# cpu.net
KiCad netlist of a schematic drawn in Altium Designer
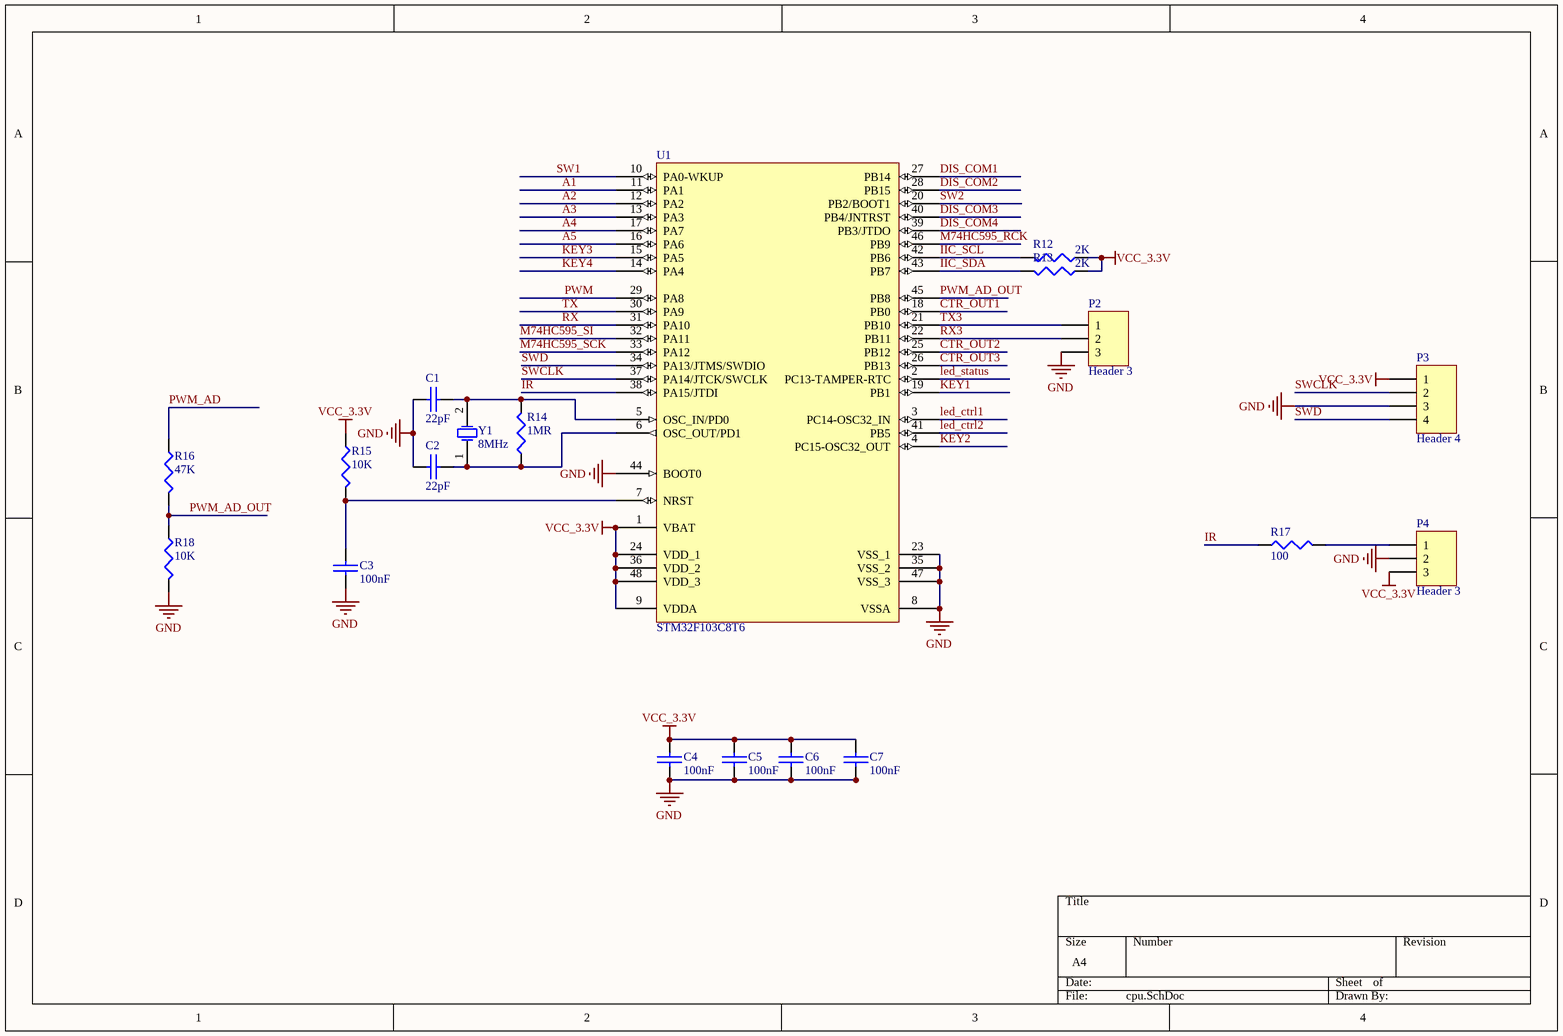
[diagram p0: cpu.SchDoc]

(export (version "E")
  (design (tool "Eeschema 10.0.6"))
  (components
    (comp (ref "C1")
      (value "22pF")
      (footprint "0805c")
      (description "Capacitor")
      (libsource (lib "SM") (part "CAP"))
    )
    (comp (ref "C2")
      (value "22pF")
      (footprint "0805c")
      (description "Capacitor")
      (libsource (lib "SM") (part "CAP"))
    )
    (comp (ref "C3")
      (value "100nF")
      (footprint "0805c")
      (description "Capacitor")
      (libsource (lib "SM") (part "CAP"))
    )
    (comp (ref "C4")
      (value "100nF")
      (footprint "0805c")
      (description "Capacitor")
      (libsource (lib "SM") (part "CAP"))
    )
    (comp (ref "C5")
      (value "100nF")
      (footprint "0805c")
      (description "Capacitor")
      (libsource (lib "SM") (part "CAP"))
    )
    (comp (ref "C6")
      (value "100nF")
      (footprint "0805c")
      (description "Capacitor")
      (libsource (lib "SM") (part "CAP"))
    )
    (comp (ref "C7")
      (value "100nF")
      (footprint "0805c")
      (description "Capacitor")
      (libsource (lib "SM") (part "CAP"))
    )
    (comp (ref "P2")
      (value "Header 3")
      (footprint "HDR1X3")
      (description "Header, 3-Pin")
      (fields (field (name "PUBLISHER") "Altium Limited"))
      (libsource (lib "Miscellaneous Connectors") (part "Header 3"))
    )
    (comp (ref "P3")
      (value "Header 4")
      (footprint "HDR1X4")
      (description "Header, 4-Pin")
      (fields (field (name "PUBLISHER") "Altium Limited"))
      (libsource (lib "Miscellaneous Connectors") (part "Header 4"))
    )
    (comp (ref "P4")
      (value "Header 3")
      (footprint "HDR1X3")
      (description "Header, 3-Pin")
      (fields (field (name "PUBLISHER") "Altium Limited"))
      (libsource (lib "Miscellaneous Connectors") (part "Header 3"))
    )
    (comp (ref "R12")
      (value "2K")
      (footprint "0805R")
      (description "Resistor")
      (fields (field (name "PUBLISHER") "Altium Limited"))
      (libsource (lib "SM") (part "Res3"))
    )
    (comp (ref "R13")
      (value "2K")
      (footprint "0805R")
      (description "Resistor")
      (fields (field (name "PUBLISHER") "Altium Limited"))
      (libsource (lib "SM") (part "Res3"))
    )
    (comp (ref "R14")
      (value "1MR")
      (footprint "0805R")
      (description "Resistor")
      (fields (field (name "PUBLISHER") "Altium Limited"))
      (libsource (lib "SM") (part "Res3"))
    )
    (comp (ref "R15")
      (value "10K")
      (footprint "0805R")
      (description "Resistor")
      (fields (field (name "PUBLISHER") "Altium Limited"))
      (libsource (lib "SM") (part "Res3"))
    )
    (comp (ref "R16")
      (value "47K")
      (footprint "0805R")
      (description "Resistor")
      (fields (field (name "PUBLISHER") "Altium Limited"))
      (libsource (lib "SM") (part "Res3"))
    )
    (comp (ref "R17")
      (value "100")
      (footprint "0805R")
      (description "Resistor")
      (fields (field (name "PUBLISHER") "Altium Limited"))
      (libsource (lib "SM") (part "Res3"))
    )
    (comp (ref "R18")
      (value "10K")
      (footprint "0805R")
      (description "Resistor")
      (fields (field (name "PUBLISHER") "Altium Limited"))
      (libsource (lib "SM") (part "Res3"))
    )
    (comp (ref "U1")
      (value "STM32F103C8T6")
      (footprint "TQFP-48")
      (description "STM32 ARM-based 32-bit MCU with 64 Kbytes Flash, 48-pin LQFP, Industrial Temperature")
      (fields (field (name "PUBLISHER") "Altium Limited"))
      (libsource (lib "ST Microcontroller 32-Bit STM32") (part "STM32F103C8T6"))
    )
    (comp (ref "Y1")
      (value "8MHz")
      (footprint "SMT5032")
      (description "Crystal Oscillator")
      (fields (field (name "PUBLISHER") "Altium Limited"))
      (libsource (lib "Miscellaneous Devices") (part "XTAL"))
    )
  )
  (nets
    (net (code "1") (name "/A1") (class "Default")
      (node (ref "U1") (pin "11") (pinfunction "PA1_11") (pintype "bidirectional"))
    )
    (net (code "2") (name "/A2") (class "Default")
      (node (ref "U1") (pin "12") (pinfunction "PA2_12") (pintype "bidirectional"))
    )
    (net (code "3") (name "/A3") (class "Default")
      (node (ref "U1") (pin "13") (pinfunction "PA3_13") (pintype "bidirectional"))
    )
    (net (code "4") (name "/A4") (class "Default")
      (node (ref "U1") (pin "17") (pinfunction "PA7_17") (pintype "bidirectional"))
    )
    (net (code "5") (name "/A5") (class "Default")
      (node (ref "U1") (pin "16") (pinfunction "PA6_16") (pintype "bidirectional"))
    )
    (net (code "6") (name "/CTR_OUT1") (class "Default")
      (node (ref "U1") (pin "18") (pinfunction "PB0_18") (pintype "bidirectional"))
    )
    (net (code "7") (name "/CTR_OUT2") (class "Default")
      (node (ref "U1") (pin "25") (pinfunction "PB12_25") (pintype "bidirectional"))
    )
    (net (code "8") (name "/CTR_OUT3") (class "Default")
      (node (ref "U1") (pin "26") (pinfunction "PB13_26") (pintype "bidirectional"))
    )
    (net (code "9") (name "/DIS_COM1") (class "Default")
      (node (ref "U1") (pin "27") (pinfunction "PB14_27") (pintype "bidirectional"))
    )
    (net (code "10") (name "/DIS_COM2") (class "Default")
      (node (ref "U1") (pin "28") (pinfunction "PB15_28") (pintype "bidirectional"))
    )
    (net (code "11") (name "/DIS_COM3") (class "Default")
      (node (ref "U1") (pin "40") (pinfunction "PB4/JNTRST_40") (pintype "bidirectional"))
    )
    (net (code "12") (name "/DIS_COM4") (class "Default")
      (node (ref "U1") (pin "39") (pinfunction "PB3/JTDO_39") (pintype "bidirectional"))
    )
    (net (code "13") (name "/IIC_SCL") (class "Default")
      (node (ref "R12") (pin "2") (pinfunction "2_2") (pintype "passive"))
      (node (ref "U1") (pin "42") (pinfunction "PB6_42") (pintype "bidirectional"))
    )
    (net (code "14") (name "/IIC_SDA") (class "Default")
      (node (ref "R13") (pin "2") (pinfunction "2_2") (pintype "passive"))
      (node (ref "U1") (pin "43") (pinfunction "PB7_43") (pintype "bidirectional"))
    )
    (net (code "15") (name "/IR") (class "Default")
      (node (ref "R17") (pin "1") (pinfunction "1_1") (pintype "passive"))
      (node (ref "U1") (pin "38") (pinfunction "PA15/JTDI_38") (pintype "bidirectional"))
    )
    (net (code "16") (name "/KEY1") (class "Default")
      (node (ref "U1") (pin "19") (pinfunction "PB1_19") (pintype "bidirectional"))
    )
    (net (code "17") (name "/KEY2") (class "Default")
      (node (ref "U1") (pin "4") (pinfunction "PC15-OSC32_OUT_4") (pintype "bidirectional"))
    )
    (net (code "18") (name "/KEY3") (class "Default")
      (node (ref "U1") (pin "15") (pinfunction "PA5_15") (pintype "bidirectional"))
    )
    (net (code "19") (name "/KEY4") (class "Default")
      (node (ref "U1") (pin "14") (pinfunction "PA4_14") (pintype "bidirectional"))
    )
    (net (code "20") (name "/M74HC595_RCK") (class "Default")
      (node (ref "U1") (pin "46") (pinfunction "PB9_46") (pintype "bidirectional"))
    )
    (net (code "21") (name "/M74HC595_SCK") (class "Default")
      (node (ref "U1") (pin "33") (pinfunction "PA12_33") (pintype "bidirectional"))
    )
    (net (code "22") (name "/M74HC595_SI") (class "Default")
      (node (ref "U1") (pin "32") (pinfunction "PA11_32") (pintype "bidirectional"))
    )
    (net (code "23") (name "/PWM") (class "Default")
      (node (ref "U1") (pin "29") (pinfunction "PA8_29") (pintype "bidirectional"))
    )
    (net (code "24") (name "/PWM_AD") (class "Default")
      (node (ref "R16") (pin "1") (pinfunction "1_1") (pintype "passive"))
    )
    (net (code "25") (name "/PWM_AD_OUT") (class "Default")
      (node (ref "R16") (pin "2") (pinfunction "2_2") (pintype "passive"))
      (node (ref "R18") (pin "1") (pinfunction "1_1") (pintype "passive"))
      (node (ref "U1") (pin "45") (pinfunction "PB8_45") (pintype "bidirectional"))
    )
    (net (code "26") (name "/RX") (class "Default")
      (node (ref "U1") (pin "31") (pinfunction "PA10_31") (pintype "bidirectional"))
    )
    (net (code "27") (name "/RX3") (class "Default")
      (node (ref "P2") (pin "2") (pinfunction "2_2") (pintype "passive"))
      (node (ref "U1") (pin "22") (pinfunction "PB11_22") (pintype "bidirectional"))
    )
    (net (code "28") (name "/SW1") (class "Default")
      (node (ref "U1") (pin "10") (pinfunction "PA0-WKUP_10") (pintype "bidirectional"))
    )
    (net (code "29") (name "/SW2") (class "Default")
      (node (ref "U1") (pin "20") (pinfunction "PB2/BOOT1_20") (pintype "bidirectional"))
    )
    (net (code "30") (name "/SWCLK") (class "Default")
      (node (ref "P3") (pin "2") (pinfunction "2_2") (pintype "passive"))
      (node (ref "U1") (pin "37") (pinfunction "PA14/JTCK/SWCLK_37") (pintype "bidirectional"))
    )
    (net (code "31") (name "/SWD") (class "Default")
      (node (ref "P3") (pin "4") (pinfunction "4_4") (pintype "passive"))
      (node (ref "U1") (pin "34") (pinfunction "PA13/JTMS/SWDIO_34") (pintype "bidirectional"))
    )
    (net (code "32") (name "/TX") (class "Default")
      (node (ref "U1") (pin "30") (pinfunction "PA9_30") (pintype "bidirectional"))
    )
    (net (code "33") (name "/TX3") (class "Default")
      (node (ref "P2") (pin "1") (pinfunction "1_1") (pintype "passive"))
      (node (ref "U1") (pin "21") (pinfunction "PB10_21") (pintype "bidirectional"))
    )
    (net (code "34") (name "/led_ctrl1") (class "Default")
      (node (ref "U1") (pin "3") (pinfunction "PC14-OSC32_IN_3") (pintype "bidirectional"))
    )
    (net (code "35") (name "/led_ctrl2") (class "Default")
      (node (ref "U1") (pin "41") (pinfunction "PB5_41") (pintype "bidirectional"))
    )
    (net (code "36") (name "/led_status") (class "Default")
      (node (ref "U1") (pin "2") (pinfunction "PC13-TAMPER-RTC_2") (pintype "bidirectional"))
    )
    (net (code "37") (name "GND") (class "Default")
      (node (ref "C1") (pin "1") (pinfunction "1_1") (pintype "passive"))
      (node (ref "C2") (pin "1") (pinfunction "1_1") (pintype "passive"))
      (node (ref "C3") (pin "1") (pinfunction "1_1") (pintype "passive"))
      (node (ref "C4") (pin "1") (pinfunction "1_1") (pintype "passive"))
      (node (ref "C5") (pin "1") (pinfunction "1_1") (pintype "passive"))
      (node (ref "C6") (pin "1") (pinfunction "1_1") (pintype "passive"))
      (node (ref "C7") (pin "1") (pinfunction "1_1") (pintype "passive"))
      (node (ref "P2") (pin "3") (pinfunction "3_3") (pintype "passive"))
      (node (ref "P3") (pin "3") (pinfunction "3_3") (pintype "passive"))
      (node (ref "P4") (pin "2") (pinfunction "2_2") (pintype "passive"))
      (node (ref "R18") (pin "2") (pinfunction "2_2") (pintype "passive"))
      (node (ref "U1") (pin "23") (pinfunction "VSS_1_23") (pintype "power_in"))
      (node (ref "U1") (pin "35") (pinfunction "VSS_2_35") (pintype "power_in"))
      (node (ref "U1") (pin "44") (pinfunction "BOOT0_44") (pintype "input"))
      (node (ref "U1") (pin "47") (pinfunction "VSS_3_47") (pintype "power_in"))
      (node (ref "U1") (pin "8") (pinfunction "VSSA_8") (pintype "power_in"))
    )
    (net (code "38") (name "Net-(P4-Pad1)") (class "Default")
      (node (ref "P4") (pin "1") (pinfunction "1_1") (pintype "passive"))
      (node (ref "R17") (pin "2") (pinfunction "2_2") (pintype "passive"))
    )
    (net (code "39") (name "Net-(U1-NRST)") (class "Default")
      (node (ref "C3") (pin "2") (pinfunction "2_2") (pintype "passive"))
      (node (ref "R15") (pin "2") (pinfunction "2_2") (pintype "passive"))
      (node (ref "U1") (pin "7") (pinfunction "NRST_7") (pintype "bidirectional"))
    )
    (net (code "40") (name "Net-(U1-OSC_IN{slash}PD0)") (class "Default")
      (node (ref "C1") (pin "2") (pinfunction "2_2") (pintype "passive"))
      (node (ref "R14") (pin "2") (pinfunction "2_2") (pintype "passive"))
      (node (ref "U1") (pin "5") (pinfunction "OSC_IN/PD0_5") (pintype "input"))
      (node (ref "Y1") (pin "2") (pinfunction "OSC2_2") (pintype "passive"))
    )
    (net (code "41") (name "Net-(U1-OSC_OUT{slash}PD1)") (class "Default")
      (node (ref "C2") (pin "2") (pinfunction "2_2") (pintype "passive"))
      (node (ref "R14") (pin "1") (pinfunction "1_1") (pintype "passive"))
      (node (ref "U1") (pin "6") (pinfunction "OSC_OUT/PD1_6") (pintype "output"))
      (node (ref "Y1") (pin "1") (pinfunction "OSC1_1") (pintype "passive"))
    )
    (net (code "42") (name "VCC_3.3V") (class "Default")
      (node (ref "C4") (pin "2") (pinfunction "2_2") (pintype "passive"))
      (node (ref "C5") (pin "2") (pinfunction "2_2") (pintype "passive"))
      (node (ref "C6") (pin "2") (pinfunction "2_2") (pintype "passive"))
      (node (ref "C7") (pin "2") (pinfunction "2_2") (pintype "passive"))
      (node (ref "P3") (pin "1") (pinfunction "1_1") (pintype "passive"))
      (node (ref "P4") (pin "3") (pinfunction "3_3") (pintype "passive"))
      (node (ref "R12") (pin "1") (pinfunction "1_1") (pintype "passive"))
      (node (ref "R13") (pin "1") (pinfunction "1_1") (pintype "passive"))
      (node (ref "R15") (pin "1") (pinfunction "1_1") (pintype "passive"))
      (node (ref "U1") (pin "1") (pinfunction "VBAT_1") (pintype "power_in"))
      (node (ref "U1") (pin "24") (pinfunction "VDD_1_24") (pintype "power_in"))
      (node (ref "U1") (pin "36") (pinfunction "VDD_2_36") (pintype "power_in"))
      (node (ref "U1") (pin "48") (pinfunction "VDD_3_48") (pintype "power_in"))
      (node (ref "U1") (pin "9") (pinfunction "VDDA_9") (pintype "power_in"))
    )
  )
)
